# OPS-Capstone-PCB.net
KiCad netlist of a schematic drawn in EAGLE
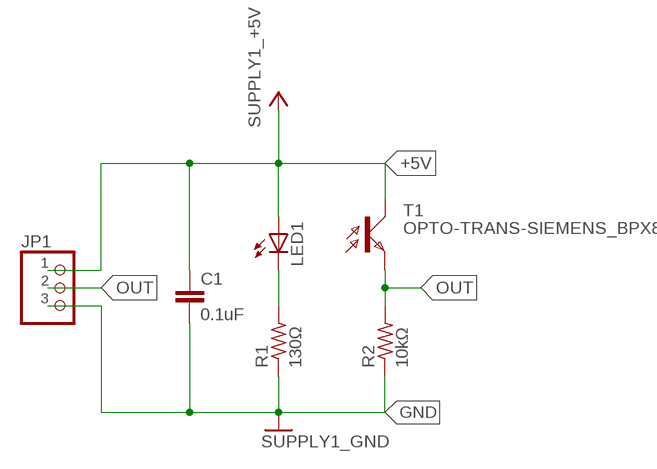
[diagram p0: schematic, sheet 1]

(export (version "E")
  (design (tool "Eeschema 10.0.6"))
  (components
    (comp (ref "C1")
      (value "0.1uF")
      (footprint "eagle-import:RCL_C1206")
      (libsource (lib "eagle-import") (part "RCL_C-EUC1206"))
    )
    (comp (ref "JP1")
      (value "PINHEAD_PINHD-1X3")
      (footprint "eagle-import:PINHEAD_1X03")
      (libsource (lib "eagle-import") (part "PINHEAD_PINHD-1X3"))
    )
    (comp (ref "LED1")
      (value "LED_LED5MM")
      (footprint "eagle-import:LED_LED5MM")
      (libsource (lib "eagle-import") (part "LED_LED5MM"))
    )
    (comp (ref "R1")
      (value "130Ω")
      (footprint "eagle-import:RCL_R1206")
      (libsource (lib "eagle-import") (part "RCL_R-US_R1206"))
    )
    (comp (ref "R2")
      (value "10kΩ")
      (footprint "eagle-import:RCL_R1206")
      (libsource (lib "eagle-import") (part "RCL_R-US_R1206"))
    )
    (comp (ref "T1")
      (value "OPTO-TRANS-SIEMENS_BPX81")
      (footprint "eagle-import:OPTO-TRANS-SIEMENS_BPX81")
      (libsource (lib "eagle-import") (part "OPTO-TRANS-SIEMENS_BPX81"))
    )
  )
  (nets
    (net (code "1") (name "+5V") (class "Default")
      (node (ref "C1") (pin "1") (pinfunction "1_1") (pintype "passive"))
      (node (ref "JP1") (pin "1") (pinfunction "1_1") (pintype "passive"))
      (node (ref "LED1") (pin "A") (pinfunction "A_A") (pintype "passive"))
      (node (ref "T1") (pin "C") (pinfunction "C_C") (pintype "passive"))
    )
    (net (code "2") (name "GND") (class "Default")
      (node (ref "C1") (pin "2") (pinfunction "2_2") (pintype "passive"))
      (node (ref "JP1") (pin "3") (pinfunction "3_3") (pintype "passive"))
      (node (ref "R1") (pin "1") (pinfunction "1_1") (pintype "passive"))
      (node (ref "R2") (pin "1") (pinfunction "1_1") (pintype "passive"))
    )
    (net (code "3") (name "Net-(LED1-C)") (class "Default")
      (node (ref "LED1") (pin "K") (pinfunction "C_K") (pintype "passive"))
      (node (ref "R1") (pin "2") (pinfunction "2_2") (pintype "passive"))
    )
    (net (code "4") (name "OUT") (class "Default")
      (node (ref "JP1") (pin "2") (pinfunction "2_2") (pintype "passive"))
      (node (ref "R2") (pin "2") (pinfunction "2_2") (pintype "passive"))
      (node (ref "T1") (pin "E") (pinfunction "E_E") (pintype "passive"))
    )
  )
)
